# POWER.net
KiCad netlist of a schematic drawn in Altium Designer
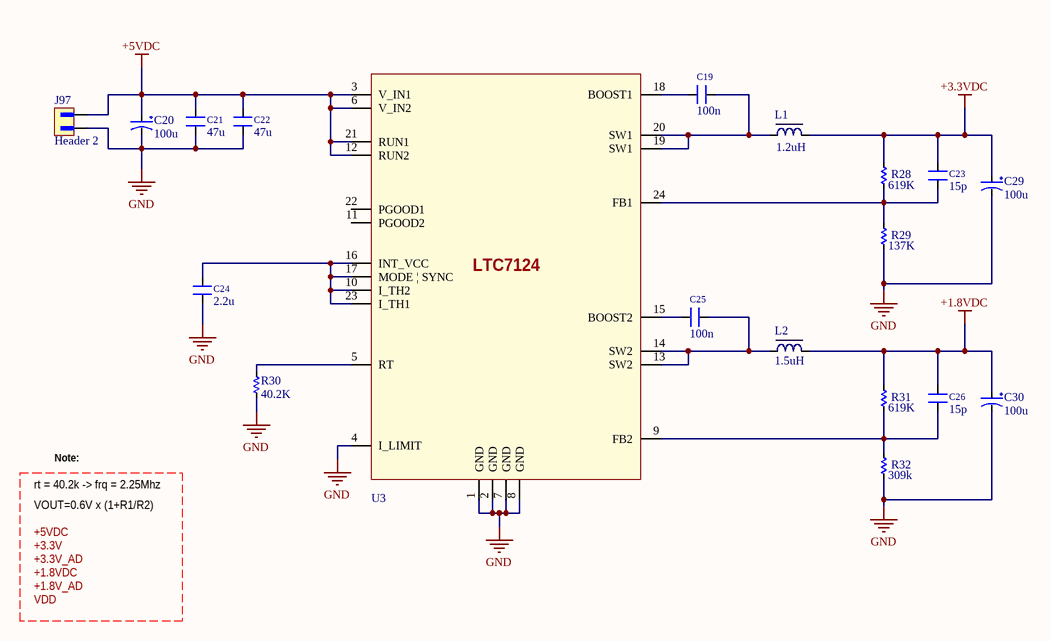
[diagram p0: POWER.SchDoc]

(export (version "E")
  (design (tool "Eeschema 10.0.6"))
  (components
    (comp (ref "C19")
      (value "100n")
      (footprint "CN-SMD-0603")
      (description "CAP SMD")
      (fields (field (name "DESIGNED BY") "VanDungEvn"))
      (libsource (lib "Sang_Library") (part "CAP SMD"))
    )
    (comp (ref "C20")
      (value "100u")
      (footprint "CAP-ALU-SMD-5x5.5x1.4")
      (description "CAP-ALU-SMD")
      (fields (field (name "PUBLISHER") "Altium Limited"))
      (libsource (lib "Sang_Library") (part "CAP-ALU-SMD"))
    )
    (comp (ref "C21")
      (value "47u")
      (footprint "SM-CAP-3225")
      (description "CAP SMD")
      (fields (field (name "DESIGNED BY") "VanDungEvn"))
      (libsource (lib "Sang_Library") (part "CAP SMD"))
    )
    (comp (ref "C22")
      (value "47u")
      (footprint "SM-CAP-3225")
      (description "CAP SMD")
      (fields (field (name "DESIGNED BY") "VanDungEvn"))
      (libsource (lib "Sang_Library") (part "CAP SMD"))
    )
    (comp (ref "C23")
      (value "15p")
      (footprint "CN-SMD-0603")
      (description "CAP SMD")
      (fields (field (name "DESIGNED BY") "VanDungEvn"))
      (libsource (lib "Sang_Library") (part "CAP SMD"))
    )
    (comp (ref "C24")
      (value "2.2u")
      (footprint "CN-SMD-0805")
      (description "CAP SMD")
      (fields (field (name "DESIGNED BY") "VanDungEvn"))
      (libsource (lib "Sang_Library") (part "CAP SMD"))
    )
    (comp (ref "C25")
      (value "100n")
      (footprint "CN-SMD-0603")
      (description "CAP SMD")
      (fields (field (name "DESIGNED BY") "VanDungEvn"))
      (libsource (lib "Sang_Library") (part "CAP SMD"))
    )
    (comp (ref "C26")
      (value "15p")
      (footprint "CN-SMD-0603")
      (description "CAP SMD")
      (fields (field (name "DESIGNED BY") "VanDungEvn"))
      (libsource (lib "Sang_Library") (part "CAP SMD"))
    )
    (comp (ref "C29")
      (value "100u")
      (footprint "CAP-ALU-SMD-5x5.5x1.4")
      (description "CAP-ALU-SMD")
      (fields (field (name "PUBLISHER") "Altium Limited"))
      (libsource (lib "Sang_Library") (part "CAP-ALU-SMD"))
    )
    (comp (ref "C30")
      (value "100u")
      (footprint "CAP-ALU-SMD-5x5.5x1.4")
      (description "CAP-ALU-SMD")
      (fields (field (name "PUBLISHER") "Altium Limited"))
      (libsource (lib "Sang_Library") (part "CAP-ALU-SMD"))
    )
    (comp (ref "J97")
      (value "Header 2")
      (footprint "JST B2B-PH-SM4-TB (LF)(SN)")
      (libsource (lib "Sang_Library") (part "Header 2"))
    )
    (comp (ref "L1")
      (value "1.2uH")
      (footprint "L-SMD-06030-7.4x6.6X3")
      (description "inductor-SMD")
      (libsource (lib "Sang_Library") (part "inductor-SMD"))
    )
    (comp (ref "L2")
      (value "1.5uH")
      (footprint "L-SMD-06030-7.4x6.6X3")
      (description "inductor-SMD")
      (libsource (lib "Sang_Library") (part "inductor-SMD"))
    )
    (comp (ref "R28")
      (value "619K")
      (footprint "RES-SMD-0603")
      (description "Resistor")
      (fields
        (field (name "MANUFACTURER") "Generic Components")
        (field (name "PUBLISHER") "Altium Hobart Technology Centre")
      )
      (libsource (lib "Sang_Library") (part "Res-SMD"))
    )
    (comp (ref "R29")
      (value "137K")
      (footprint "RES-SMD-0603")
      (description "Resistor")
      (fields
        (field (name "MANUFACTURER") "Generic Components")
        (field (name "PUBLISHER") "Altium Hobart Technology Centre")
      )
      (libsource (lib "Sang_Library") (part "Res-SMD"))
    )
    (comp (ref "R30")
      (value "40.2K")
      (footprint "RES-SMD-0603")
      (description "Resistor")
      (fields
        (field (name "MANUFACTURER") "Generic Components")
        (field (name "PUBLISHER") "Altium Hobart Technology Centre")
      )
      (libsource (lib "Sang_Library") (part "Res-SMD"))
    )
    (comp (ref "R31")
      (value "619K")
      (footprint "RES-SMD-0603")
      (description "Resistor")
      (fields
        (field (name "MANUFACTURER") "Generic Components")
        (field (name "PUBLISHER") "Altium Hobart Technology Centre")
      )
      (libsource (lib "Sang_Library") (part "Res-SMD"))
    )
    (comp (ref "R32")
      (value "309k")
      (footprint "RES-SMD-0603")
      (description "Resistor")
      (fields
        (field (name "MANUFACTURER") "Generic Components")
        (field (name "PUBLISHER") "Altium Hobart Technology Centre")
      )
      (libsource (lib "Sang_Library") (part "Res-SMD"))
    )
    (comp (ref "U3")
      (value "LTC7124")
      (footprint "24-Lead Plastic QFN (3mm × 5mm)")
      (description "17V, Dual 3.5A Synchronous Step-Down  \r\nRegulator with Ultralow Quiescent Current")
      (libsource (lib "Huan") (part "LTC7124"))
    )
  )
  (nets
    (net (code "1") (name "+1.8VDC") (class "Default")
      (node (ref "C26") (pin "1") (pinfunction "1_1") (pintype "passive"))
      (node (ref "C30") (pin "1") (pinfunction "1_1") (pintype "passive"))
      (node (ref "L2") (pin "2") (pinfunction "2_2") (pintype "passive"))
      (node (ref "R31") (pin "2") (pinfunction "2_2") (pintype "passive"))
    )
    (net (code "2") (name "+3.3VDC") (class "Default")
      (node (ref "C23") (pin "1") (pinfunction "1_1") (pintype "passive"))
      (node (ref "C29") (pin "1") (pinfunction "1_1") (pintype "passive"))
      (node (ref "L1") (pin "2") (pinfunction "2_2") (pintype "passive"))
      (node (ref "R28") (pin "2") (pinfunction "2_2") (pintype "passive"))
    )
    (net (code "3") (name "+5VDC") (class "Default")
      (node (ref "C20") (pin "1") (pinfunction "1_1") (pintype "passive"))
      (node (ref "C21") (pin "2") (pinfunction "2_2") (pintype "passive"))
      (node (ref "C22") (pin "2") (pinfunction "2_2") (pintype "passive"))
      (node (ref "J97") (pin "2") (pinfunction "2_2") (pintype "passive"))
      (node (ref "U3") (pin "12") (pinfunction "RUN2_12") (pintype "passive"))
      (node (ref "U3") (pin "21") (pinfunction "RUN1_21") (pintype "passive"))
      (node (ref "U3") (pin "3") (pinfunction "V_IN1_3") (pintype "passive"))
      (node (ref "U3") (pin "6") (pinfunction "V_IN2_6") (pintype "passive"))
    )
    (net (code "4") (name "GND") (class "Default")
      (node (ref "C20") (pin "2") (pinfunction "2_2") (pintype "passive"))
      (node (ref "C21") (pin "1") (pinfunction "1_1") (pintype "passive"))
      (node (ref "C22") (pin "1") (pinfunction "1_1") (pintype "passive"))
      (node (ref "C24") (pin "1") (pinfunction "1_1") (pintype "passive"))
      (node (ref "C29") (pin "2") (pinfunction "2_2") (pintype "passive"))
      (node (ref "C30") (pin "2") (pinfunction "2_2") (pintype "passive"))
      (node (ref "J97") (pin "1") (pinfunction "1_1") (pintype "passive"))
      (node (ref "R29") (pin "1") (pinfunction "1_1") (pintype "passive"))
      (node (ref "R30") (pin "1") (pinfunction "1_1") (pintype "passive"))
      (node (ref "R32") (pin "1") (pinfunction "1_1") (pintype "passive"))
      (node (ref "U3") (pin "1") (pinfunction "GND_1") (pintype "passive"))
      (node (ref "U3") (pin "2") (pinfunction "GND_2") (pintype "passive"))
      (node (ref "U3") (pin "4") (pinfunction "I_LIMIT_4") (pintype "passive"))
      (node (ref "U3") (pin "7") (pinfunction "GND_7") (pintype "passive"))
      (node (ref "U3") (pin "8") (pinfunction "GND_8") (pintype "passive"))
    )
    (net (code "5") (name "Net-(C19-Pad1)") (class "Default")
      (node (ref "C19") (pin "1") (pinfunction "1_1") (pintype "passive"))
      (node (ref "L1") (pin "1") (pinfunction "1_1") (pintype "passive"))
      (node (ref "U3") (pin "19") (pinfunction "SW1_19") (pintype "passive"))
      (node (ref "U3") (pin "20") (pinfunction "SW1_20") (pintype "passive"))
    )
    (net (code "6") (name "Net-(C25-Pad1)") (class "Default")
      (node (ref "C25") (pin "1") (pinfunction "1_1") (pintype "passive"))
      (node (ref "L2") (pin "1") (pinfunction "1_1") (pintype "passive"))
      (node (ref "U3") (pin "13") (pinfunction "SW2_13") (pintype "passive"))
      (node (ref "U3") (pin "14") (pinfunction "SW2_14") (pintype "passive"))
    )
    (net (code "7") (name "Net-(U3-BOOST1)") (class "Default")
      (node (ref "C19") (pin "2") (pinfunction "2_2") (pintype "passive"))
      (node (ref "U3") (pin "18") (pinfunction "BOOST1_18") (pintype "passive"))
    )
    (net (code "8") (name "Net-(U3-BOOST2)") (class "Default")
      (node (ref "C25") (pin "2") (pinfunction "2_2") (pintype "passive"))
      (node (ref "U3") (pin "15") (pinfunction "BOOST2_15") (pintype "passive"))
    )
    (net (code "9") (name "Net-(U3-FB1)") (class "Default")
      (node (ref "C23") (pin "2") (pinfunction "2_2") (pintype "passive"))
      (node (ref "R28") (pin "1") (pinfunction "1_1") (pintype "passive"))
      (node (ref "R29") (pin "2") (pinfunction "2_2") (pintype "passive"))
      (node (ref "U3") (pin "24") (pinfunction "FB1_24") (pintype "passive"))
    )
    (net (code "10") (name "Net-(U3-FB2)") (class "Default")
      (node (ref "C26") (pin "2") (pinfunction "2_2") (pintype "passive"))
      (node (ref "R31") (pin "1") (pinfunction "1_1") (pintype "passive"))
      (node (ref "R32") (pin "2") (pinfunction "2_2") (pintype "passive"))
      (node (ref "U3") (pin "9") (pinfunction "FB2_9") (pintype "passive"))
    )
    (net (code "11") (name "Net-(U3-INT_VCC)") (class "Default")
      (node (ref "C24") (pin "2") (pinfunction "2_2") (pintype "passive"))
      (node (ref "U3") (pin "10") (pinfunction "I_TH2_10") (pintype "passive"))
      (node (ref "U3") (pin "16") (pinfunction "INT_VCC_16") (pintype "passive"))
      (node (ref "U3") (pin "17") (pinfunction "MODE_¦_SYNC_17") (pintype "passive"))
      (node (ref "U3") (pin "23") (pinfunction "I_TH1_23") (pintype "passive"))
    )
    (net (code "12") (name "Net-(U3-RT)") (class "Default")
      (node (ref "R30") (pin "2") (pinfunction "2_2") (pintype "passive"))
      (node (ref "U3") (pin "5") (pinfunction "RT_5") (pintype "passive"))
    )
    (net (code "13") (name "unconnected-(U3-PGOOD1-Pad22)") (class "Default")
      (node (ref "U3") (pin "22") (pinfunction "PGOOD1_22") (pintype "passive"))
    )
    (net (code "14") (name "unconnected-(U3-PGOOD2-Pad11)") (class "Default")
      (node (ref "U3") (pin "11") (pinfunction "PGOOD2_11") (pintype "passive"))
    )
  )
)
